# Buffer.net
KiCad netlist of a schematic drawn in Altium Designer
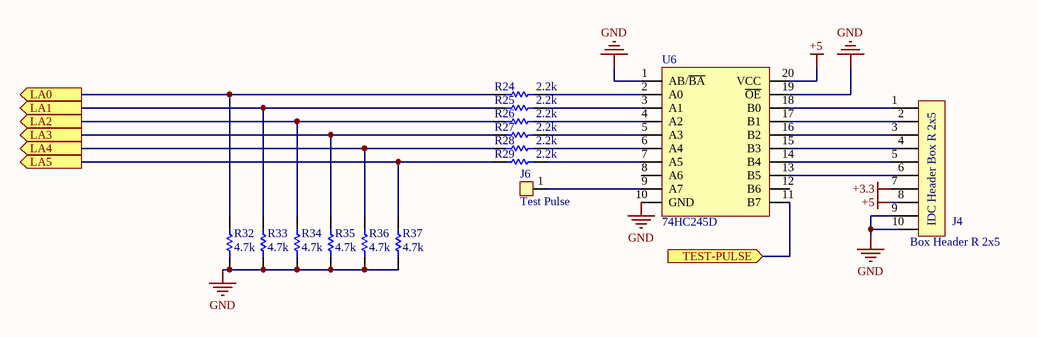
[diagram p0: Buffer.SchDoc]

(export (version "E")
  (design (tool "Eeschema 10.0.6"))
  (components
    (comp (ref "J4")
      (value "Box Header R 2x5")
      (footprint "HB-R-10")
      (description "IDC BOX HEADER RIGHT 2x5 , 2.54MM , 10 Position")
      (libsource (lib "IOElectro") (part "DS1013-10R"))
    )
    (comp (ref "J6")
      (value "Test Pulse")
      (footprint "PH-1X1-N3D")
      (description "PIN HEADER 1x1 2.56mm")
      (libsource (lib "IOElectro") (part "PH-1X1"))
    )
    (comp (ref "R24")
      (value "2.2k")
      (footprint "R-0805")
      (description "0805")
      (libsource (lib "IOElectro") (part "RES"))
    )
    (comp (ref "R25")
      (value "2.2k")
      (footprint "R-0805")
      (description "0805")
      (libsource (lib "IOElectro") (part "RES"))
    )
    (comp (ref "R26")
      (value "2.2k")
      (footprint "R-0805")
      (description "0805")
      (libsource (lib "IOElectro") (part "RES"))
    )
    (comp (ref "R27")
      (value "2.2k")
      (footprint "R-0805")
      (description "0805")
      (libsource (lib "IOElectro") (part "RES"))
    )
    (comp (ref "R28")
      (value "2.2k")
      (footprint "R-0805")
      (description "0805")
      (libsource (lib "IOElectro") (part "RES"))
    )
    (comp (ref "R29")
      (value "2.2k")
      (footprint "R-0805")
      (description "0805")
      (libsource (lib "IOElectro") (part "RES"))
    )
    (comp (ref "R32")
      (value "4.7k")
      (footprint "R-0805")
      (description "0805")
      (libsource (lib "IOElectro") (part "RES"))
    )
    (comp (ref "R33")
      (value "4.7k")
      (footprint "R-0805")
      (description "0805")
      (libsource (lib "IOElectro") (part "RES"))
    )
    (comp (ref "R34")
      (value "4.7k")
      (footprint "R-0805")
      (description "0805")
      (libsource (lib "IOElectro") (part "RES"))
    )
    (comp (ref "R35")
      (value "4.7k")
      (footprint "R-0805")
      (description "0805")
      (libsource (lib "IOElectro") (part "RES"))
    )
    (comp (ref "R36")
      (value "4.7k")
      (footprint "R-0805")
      (description "0805")
      (libsource (lib "IOElectro") (part "RES"))
    )
    (comp (ref "R37")
      (value "4.7k")
      (footprint "R-0805")
      (description "0805")
      (libsource (lib "IOElectro") (part "RES"))
    )
    (comp (ref "U6")
      (value "74HC245D")
      (footprint "SOW-20")
      (description "74HC Series 6V Surface Mount 3-State Octal Bus Transceiver - SOIC-20")
      (fields
        (field (name "MANUFACTURER") "Nexperia")
        (field (name "MANUFACTURER PART NUMBER") "74HC245D,653")
      )
      (libsource (lib "IOElectro") (part "74HC245D"))
    )
  )
  (nets
    (net (code "1") (name "+3.3") (class "Default")
      (node (ref "J4") (pin "7") (pinfunction "7_7") (pintype "passive"))
    )
    (net (code "2") (name "+5") (class "Default")
      (node (ref "J4") (pin "8") (pinfunction "8_8") (pintype "passive"))
      (node (ref "U6") (pin "20") (pinfunction "VCC_20") (pintype "passive"))
    )
    (net (code "3") (name "/LA0") (class "Default")
      (node (ref "R24") (pin "2") (pinfunction "2_2") (pintype "passive"))
      (node (ref "R32") (pin "1") (pinfunction "1_1") (pintype "passive"))
    )
    (net (code "4") (name "/LA1") (class "Default")
      (node (ref "R25") (pin "2") (pinfunction "2_2") (pintype "passive"))
      (node (ref "R33") (pin "1") (pinfunction "1_1") (pintype "passive"))
    )
    (net (code "5") (name "/LA2") (class "Default")
      (node (ref "R26") (pin "2") (pinfunction "2_2") (pintype "passive"))
      (node (ref "R34") (pin "1") (pinfunction "1_1") (pintype "passive"))
    )
    (net (code "6") (name "/LA3") (class "Default")
      (node (ref "R27") (pin "2") (pinfunction "2_2") (pintype "passive"))
      (node (ref "R35") (pin "1") (pinfunction "1_1") (pintype "passive"))
    )
    (net (code "7") (name "/LA4") (class "Default")
      (node (ref "R28") (pin "2") (pinfunction "2_2") (pintype "passive"))
      (node (ref "R36") (pin "1") (pinfunction "1_1") (pintype "passive"))
    )
    (net (code "8") (name "/LA5") (class "Default")
      (node (ref "R29") (pin "2") (pinfunction "2_2") (pintype "passive"))
      (node (ref "R37") (pin "1") (pinfunction "1_1") (pintype "passive"))
    )
    (net (code "9") (name "/TEST-PULSE") (class "Default")
      (node (ref "U6") (pin "11") (pinfunction "B7_11") (pintype "passive"))
    )
    (net (code "10") (name "GND") (class "Default")
      (node (ref "J4") (pin "10") (pinfunction "10_10") (pintype "passive"))
      (node (ref "J4") (pin "9") (pinfunction "9_9") (pintype "passive"))
      (node (ref "R32") (pin "2") (pinfunction "2_2") (pintype "passive"))
      (node (ref "R33") (pin "2") (pinfunction "2_2") (pintype "passive"))
      (node (ref "R34") (pin "2") (pinfunction "2_2") (pintype "passive"))
      (node (ref "R35") (pin "2") (pinfunction "2_2") (pintype "passive"))
      (node (ref "R36") (pin "2") (pinfunction "2_2") (pintype "passive"))
      (node (ref "R37") (pin "2") (pinfunction "2_2") (pintype "passive"))
      (node (ref "U6") (pin "1") (pinfunction "AB/~{BA}_1") (pintype "passive"))
      (node (ref "U6") (pin "10") (pinfunction "GND_10") (pintype "passive"))
      (node (ref "U6") (pin "19") (pinfunction "~{OE}_19") (pintype "passive"))
    )
    (net (code "11") (name "Net-(U6-A0)") (class "Default")
      (node (ref "R24") (pin "1") (pinfunction "1_1") (pintype "passive"))
      (node (ref "U6") (pin "2") (pinfunction "A0_2") (pintype "passive"))
    )
    (net (code "12") (name "Net-(U6-A1)") (class "Default")
      (node (ref "R25") (pin "1") (pinfunction "1_1") (pintype "passive"))
      (node (ref "U6") (pin "3") (pinfunction "A1_3") (pintype "passive"))
    )
    (net (code "13") (name "Net-(U6-A2)") (class "Default")
      (node (ref "R26") (pin "1") (pinfunction "1_1") (pintype "passive"))
      (node (ref "U6") (pin "4") (pinfunction "A2_4") (pintype "passive"))
    )
    (net (code "14") (name "Net-(U6-A3)") (class "Default")
      (node (ref "R27") (pin "1") (pinfunction "1_1") (pintype "passive"))
      (node (ref "U6") (pin "5") (pinfunction "A3_5") (pintype "passive"))
    )
    (net (code "15") (name "Net-(U6-A4)") (class "Default")
      (node (ref "R28") (pin "1") (pinfunction "1_1") (pintype "passive"))
      (node (ref "U6") (pin "6") (pinfunction "A4_6") (pintype "passive"))
    )
    (net (code "16") (name "Net-(U6-A5)") (class "Default")
      (node (ref "R29") (pin "1") (pinfunction "1_1") (pintype "passive"))
      (node (ref "U6") (pin "7") (pinfunction "A5_7") (pintype "passive"))
    )
    (net (code "17") (name "Net-(U6-A7)") (class "Default")
      (node (ref "J6") (pin "1") (pinfunction "1_1") (pintype "passive"))
      (node (ref "U6") (pin "9") (pinfunction "A7_9") (pintype "passive"))
    )
    (net (code "18") (name "Net-(U6-B0)") (class "Default")
      (node (ref "J4") (pin "1") (pinfunction "1_1") (pintype "passive"))
      (node (ref "U6") (pin "18") (pinfunction "B0_18") (pintype "passive"))
    )
    (net (code "19") (name "Net-(U6-B1)") (class "Default")
      (node (ref "J4") (pin "2") (pinfunction "2_2") (pintype "passive"))
      (node (ref "U6") (pin "17") (pinfunction "B1_17") (pintype "passive"))
    )
    (net (code "20") (name "Net-(U6-B2)") (class "Default")
      (node (ref "J4") (pin "3") (pinfunction "3_3") (pintype "passive"))
      (node (ref "U6") (pin "16") (pinfunction "B2_16") (pintype "passive"))
    )
    (net (code "21") (name "Net-(U6-B3)") (class "Default")
      (node (ref "J4") (pin "4") (pinfunction "4_4") (pintype "passive"))
      (node (ref "U6") (pin "15") (pinfunction "B3_15") (pintype "passive"))
    )
    (net (code "22") (name "Net-(U6-B4)") (class "Default")
      (node (ref "J4") (pin "5") (pinfunction "5_5") (pintype "passive"))
      (node (ref "U6") (pin "14") (pinfunction "B4_14") (pintype "passive"))
    )
    (net (code "23") (name "Net-(U6-B5)") (class "Default")
      (node (ref "J4") (pin "6") (pinfunction "6_6") (pintype "passive"))
      (node (ref "U6") (pin "13") (pinfunction "B5_13") (pintype "passive"))
    )
    (net (code "24") (name "unconnected-(U6-A6-Pad8)") (class "Default")
      (node (ref "U6") (pin "8") (pinfunction "A6_8") (pintype "passive"))
    )
    (net (code "25") (name "unconnected-(U6-B6-Pad12)") (class "Default")
      (node (ref "U6") (pin "12") (pinfunction "B6_12") (pintype "passive"))
    )
  )
)
